# flight_comp_v3.net
KiCad netlist of a schematic drawn in EAGLE
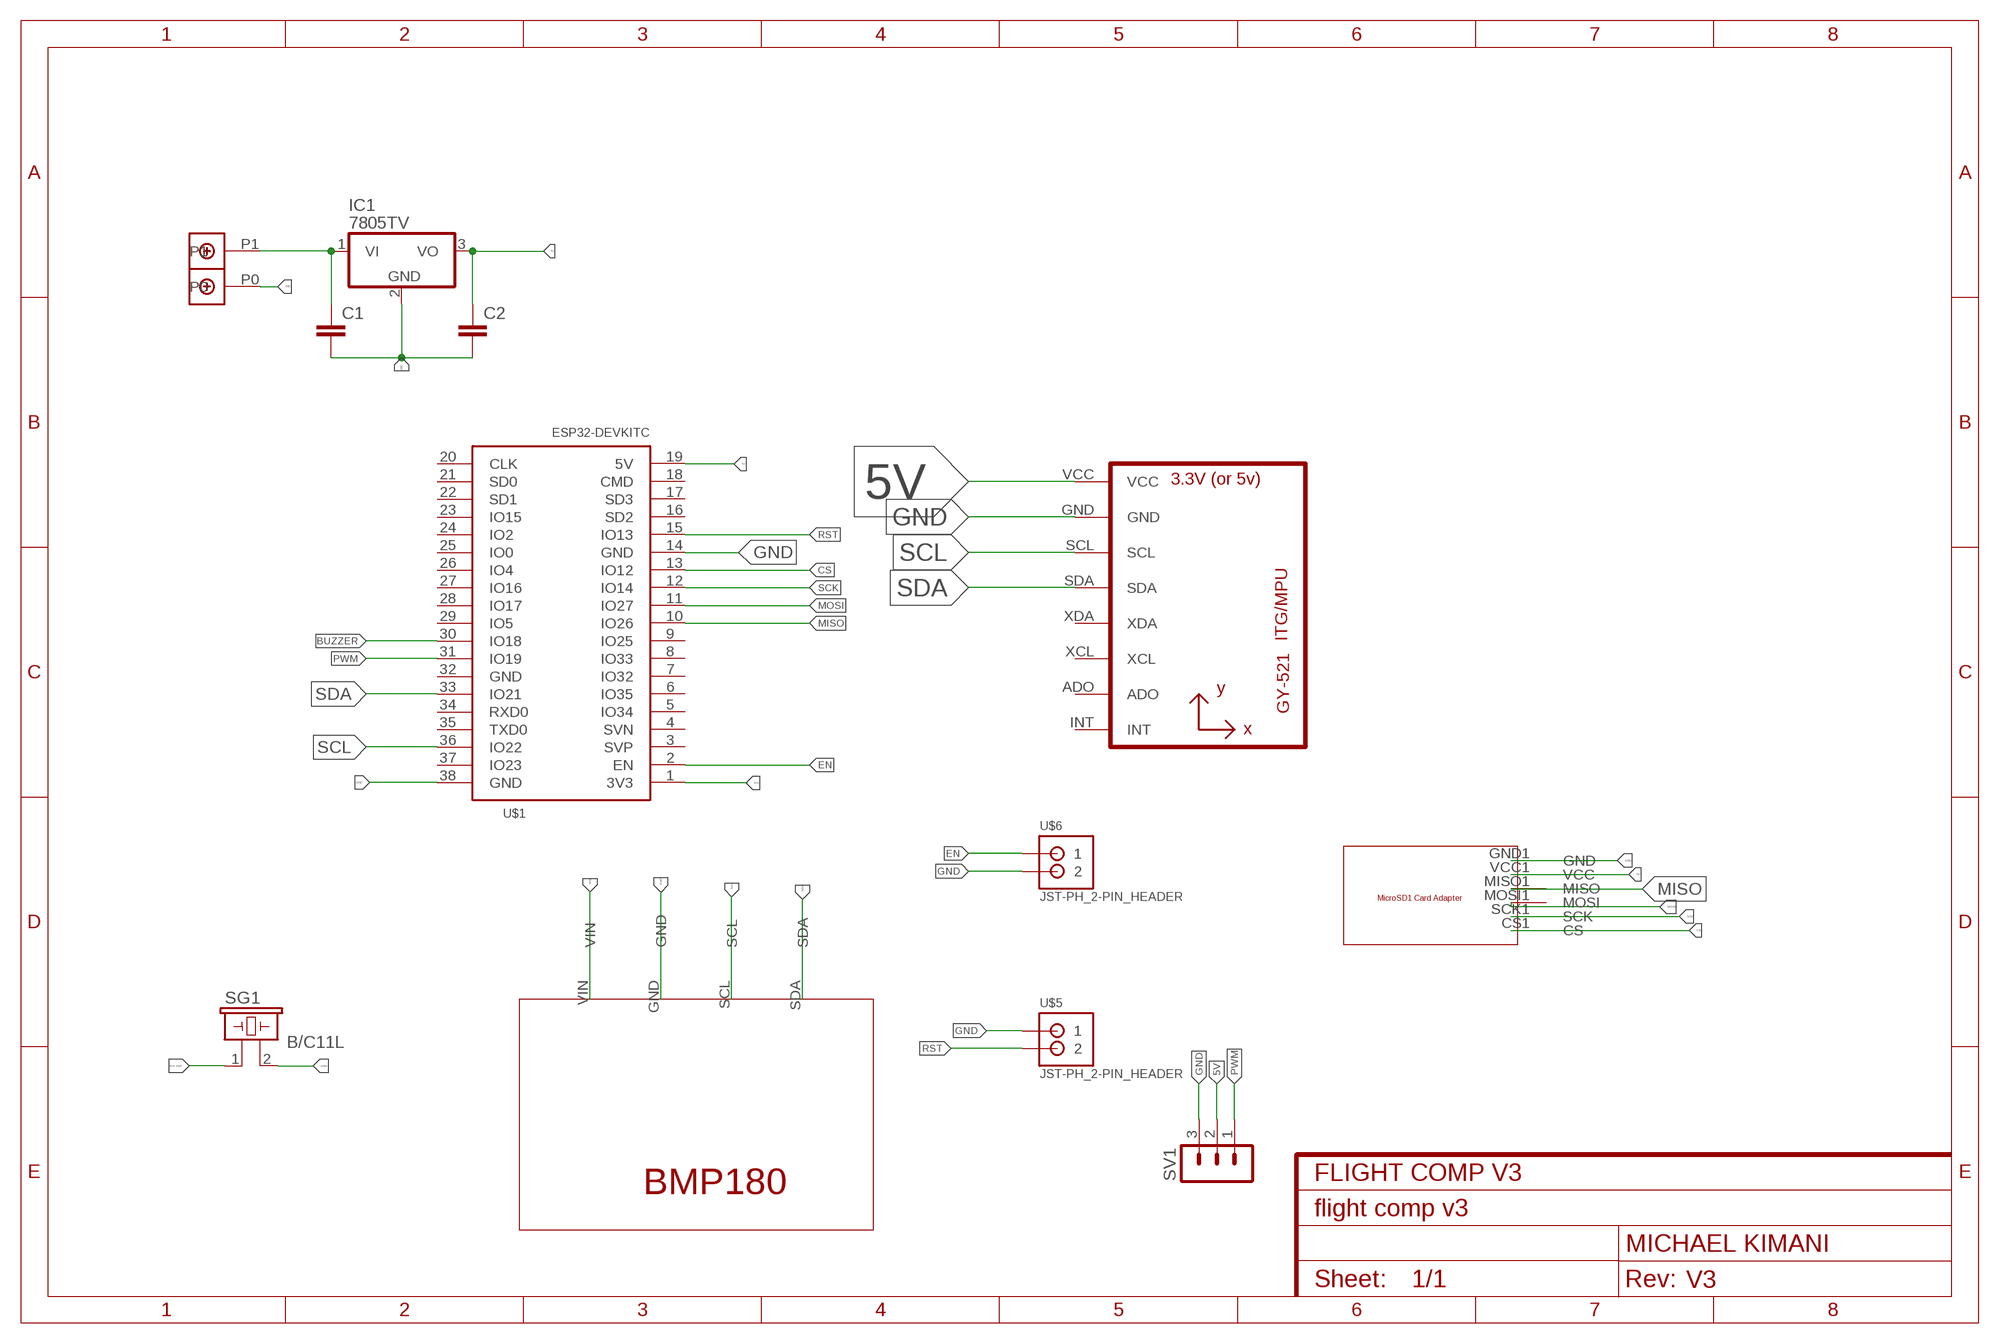
[diagram p0: schematic, sheet 1]

(export (version "E")
  (design (tool "Eeschema 10.0.6"))
  (components
    (comp (ref "C1")
      (value "C2,5-3")
      (footprint "eagle-import:C2.5-3")
      (libsource (lib "eagle-import") (part "C2,5-3"))
    )
    (comp (ref "C2")
      (value "C2,5-3")
      (footprint "eagle-import:C2.5-3")
      (libsource (lib "eagle-import") (part "C2,5-3"))
    )
    (comp (ref "IC1")
      (value "7805TV")
      (footprint "eagle-import:TO220V")
      (libsource (lib "eagle-import") (part "78TV05"))
    )
    (comp (ref "SG1")
      (value "B/C11L")
      (footprint "eagle-import:B_C11L")
      (libsource (lib "eagle-import") (part "B/C11L"))
    )
    (comp (ref "SV1")
      (value "MA03-1")
      (footprint "eagle-import:MA03-1")
      (libsource (lib "eagle-import") (part "MA03-1"))
    )
    (comp (ref "U$1")
      (value "ESP32DEVKITC")
      (footprint "eagle-import:ESP32-DEVKITC")
      (libsource (lib "eagle-import") (part "ESP32DEVKITC"))
    )
    (comp (ref "U$2")
      (value "MICROSDADAPTER")
      (footprint "eagle-import:MICROSDADAPTER")
      (libsource (lib "eagle-import") (part "MICROSDADAPTER"))
    )
    (comp (ref "U$3")
      (value "BMP180")
      (footprint "eagle-import:BMP180")
      (libsource (lib "eagle-import") (part "BMP180"))
    )
    (comp (ref "U$4")
      (value "DBCONN-1X2")
      (footprint "eagle-import:DBCONN-1X2")
      (libsource (lib "eagle-import") (part "DBCONN-1X2"))
    )
    (comp (ref "U$5")
      (value "JST-PH_2-PIN_HEADER")
      (footprint "eagle-import:JST_B2B-PH_HEADER")
      (libsource (lib "eagle-import") (part "JST-PH_2-PIN_HEADER"))
    )
    (comp (ref "U$6")
      (value "JST-PH_2-PIN_HEADER")
      (footprint "eagle-import:JST_B2B-PH_HEADER")
      (libsource (lib "eagle-import") (part "JST-PH_2-PIN_HEADER"))
    )
    (comp (ref "U1")
      (value "GY-521MPU6050")
      (footprint "eagle-import:GY-521")
      (libsource (lib "eagle-import") (part "GY-521MPU6050"))
    )
  )
  (nets
    (net (code "1") (name "3V3") (class "Default")
      (node (ref "U$1") (pin "1") (pinfunction "3V3_1") (pintype "bidirectional"))
      (node (ref "U$3") (pin "VIN") (pinfunction "VIN_VIN") (pintype "bidirectional"))
    )
    (net (code "2") (name "5V") (class "Default")
      (node (ref "C2") (pin "1") (pinfunction "1_1") (pintype "passive"))
      (node (ref "IC1") (pin "3") (pinfunction "VO_3") (pintype "passive"))
      (node (ref "SV1") (pin "2") (pinfunction "2_2") (pintype "passive"))
      (node (ref "U$1") (pin "19") (pinfunction "5V_19") (pintype "bidirectional"))
      (node (ref "U$2") (pin "VCC1") (pinfunction "VCC_VCC1") (pintype "bidirectional"))
      (node (ref "U1") (pin "VCC") (pinfunction "VCC_VCC") (pintype "bidirectional"))
    )
    (net (code "3") (name "BUZZER") (class "Default")
      (node (ref "SG1") (pin "1") (pinfunction "1_1") (pintype "passive"))
      (node (ref "U$1") (pin "30") (pinfunction "IO18_30") (pintype "bidirectional"))
    )
    (net (code "4") (name "CS") (class "Default")
      (node (ref "U$1") (pin "13") (pinfunction "IO12_13") (pintype "bidirectional"))
      (node (ref "U$2") (pin "CS1") (pinfunction "CS_CS1") (pintype "bidirectional"))
    )
    (net (code "5") (name "EN") (class "Default")
      (node (ref "U$1") (pin "2") (pinfunction "EN_2") (pintype "bidirectional"))
      (node (ref "U$6") (pin "P1") (pinfunction "1_P1") (pintype "bidirectional"))
    )
    (net (code "6") (name "GND") (class "Default")
      (node (ref "C1") (pin "2") (pinfunction "2_2") (pintype "passive"))
      (node (ref "C2") (pin "2") (pinfunction "2_2") (pintype "passive"))
      (node (ref "IC1") (pin "2") (pinfunction "GND_2") (pintype "passive"))
      (node (ref "SG1") (pin "2") (pinfunction "2_2") (pintype "passive"))
      (node (ref "SV1") (pin "3") (pinfunction "3_3") (pintype "passive"))
      (node (ref "U$1") (pin "14") (pinfunction "GND_14") (pintype "bidirectional"))
      (node (ref "U$1") (pin "38") (pinfunction "GND_38") (pintype "bidirectional"))
      (node (ref "U$2") (pin "GND1") (pinfunction "GND_GND1") (pintype "bidirectional"))
      (node (ref "U$3") (pin "GND") (pinfunction "GND_GND") (pintype "bidirectional"))
      (node (ref "U$4") (pin "P0") (pinfunction "P0_P0") (pintype "bidirectional"))
      (node (ref "U$5") (pin "P1") (pinfunction "1_P1") (pintype "bidirectional"))
      (node (ref "U$6") (pin "P2") (pinfunction "2_P2") (pintype "bidirectional"))
      (node (ref "U1") (pin "GND") (pinfunction "GND_GND") (pintype "bidirectional"))
    )
    (net (code "7") (name "MISO") (class "Default")
      (node (ref "U$1") (pin "10") (pinfunction "IO26_10") (pintype "bidirectional"))
      (node (ref "U$2") (pin "MISO1") (pinfunction "MISO_MISO1") (pintype "bidirectional"))
    )
    (net (code "8") (name "MOSI") (class "Default")
      (node (ref "U$1") (pin "11") (pinfunction "IO27_11") (pintype "bidirectional"))
      (node (ref "U$2") (pin "MOSI1") (pinfunction "MOSI_MOSI1") (pintype "bidirectional"))
    )
    (net (code "9") (name "Net-(IC1-VI)") (class "Default")
      (node (ref "C1") (pin "1") (pinfunction "1_1") (pintype "passive"))
      (node (ref "IC1") (pin "1") (pinfunction "VI_1") (pintype "input"))
      (node (ref "U$4") (pin "P1") (pinfunction "P1_P1") (pintype "bidirectional"))
    )
    (net (code "10") (name "PWM") (class "Default")
      (node (ref "SV1") (pin "1") (pinfunction "1_1") (pintype "passive"))
      (node (ref "U$1") (pin "31") (pinfunction "IO19_31") (pintype "bidirectional"))
    )
    (net (code "11") (name "RST") (class "Default")
      (node (ref "U$1") (pin "15") (pinfunction "IO13_15") (pintype "bidirectional"))
      (node (ref "U$5") (pin "P2") (pinfunction "2_P2") (pintype "bidirectional"))
    )
    (net (code "12") (name "SCK") (class "Default")
      (node (ref "U$1") (pin "12") (pinfunction "IO14_12") (pintype "bidirectional"))
      (node (ref "U$2") (pin "SCK1") (pinfunction "SCK_SCK1") (pintype "bidirectional"))
    )
    (net (code "13") (name "SCL") (class "Default")
      (node (ref "U$1") (pin "36") (pinfunction "IO22_36") (pintype "bidirectional"))
      (node (ref "U$3") (pin "SCL") (pinfunction "SCL_SCL") (pintype "bidirectional"))
      (node (ref "U1") (pin "SCL") (pinfunction "SCL_SCL") (pintype "bidirectional"))
    )
    (net (code "14") (name "SDA") (class "Default")
      (node (ref "U$1") (pin "33") (pinfunction "IO21_33") (pintype "bidirectional"))
      (node (ref "U$3") (pin "SDA") (pinfunction "SDA_SDA") (pintype "bidirectional"))
      (node (ref "U1") (pin "SDA") (pinfunction "SDA_SDA") (pintype "bidirectional"))
    )
    (net (code "15") (name "unconnected-(U$1-CLK-Pad20)") (class "Default")
      (node (ref "U$1") (pin "20") (pinfunction "CLK_20") (pintype "bidirectional"))
    )
    (net (code "16") (name "unconnected-(U$1-CMD-Pad18)") (class "Default")
      (node (ref "U$1") (pin "18") (pinfunction "CMD_18") (pintype "bidirectional"))
    )
    (net (code "17") (name "unconnected-(U$1-GND-Pad32)") (class "Default")
      (node (ref "U$1") (pin "32") (pinfunction "GND_32") (pintype "bidirectional"))
    )
    (net (code "18") (name "unconnected-(U$1-IO0-Pad25)") (class "Default")
      (node (ref "U$1") (pin "25") (pinfunction "IO0_25") (pintype "bidirectional"))
    )
    (net (code "19") (name "unconnected-(U$1-IO2-Pad24)") (class "Default")
      (node (ref "U$1") (pin "24") (pinfunction "IO2_24") (pintype "bidirectional"))
    )
    (net (code "20") (name "unconnected-(U$1-IO4-Pad26)") (class "Default")
      (node (ref "U$1") (pin "26") (pinfunction "IO4_26") (pintype "bidirectional"))
    )
    (net (code "21") (name "unconnected-(U$1-IO5-Pad29)") (class "Default")
      (node (ref "U$1") (pin "29") (pinfunction "IO5_29") (pintype "bidirectional"))
    )
    (net (code "22") (name "unconnected-(U$1-IO15-Pad23)") (class "Default")
      (node (ref "U$1") (pin "23") (pinfunction "IO15_23") (pintype "bidirectional"))
    )
    (net (code "23") (name "unconnected-(U$1-IO16-Pad27)") (class "Default")
      (node (ref "U$1") (pin "27") (pinfunction "IO16_27") (pintype "bidirectional"))
    )
    (net (code "24") (name "unconnected-(U$1-IO17-Pad28)") (class "Default")
      (node (ref "U$1") (pin "28") (pinfunction "IO17_28") (pintype "bidirectional"))
    )
    (net (code "25") (name "unconnected-(U$1-IO23-Pad37)") (class "Default")
      (node (ref "U$1") (pin "37") (pinfunction "IO23_37") (pintype "bidirectional"))
    )
    (net (code "26") (name "unconnected-(U$1-IO25-Pad9)") (class "Default")
      (node (ref "U$1") (pin "9") (pinfunction "IO25_9") (pintype "bidirectional"))
    )
    (net (code "27") (name "unconnected-(U$1-IO32-Pad7)") (class "Default")
      (node (ref "U$1") (pin "7") (pinfunction "IO32_7") (pintype "bidirectional"))
    )
    (net (code "28") (name "unconnected-(U$1-IO33-Pad8)") (class "Default")
      (node (ref "U$1") (pin "8") (pinfunction "IO33_8") (pintype "bidirectional"))
    )
    (net (code "29") (name "unconnected-(U$1-IO34-Pad5)") (class "Default")
      (node (ref "U$1") (pin "5") (pinfunction "IO34_5") (pintype "bidirectional"))
    )
    (net (code "30") (name "unconnected-(U$1-IO35-Pad6)") (class "Default")
      (node (ref "U$1") (pin "6") (pinfunction "IO35_6") (pintype "bidirectional"))
    )
    (net (code "31") (name "unconnected-(U$1-RXD0-Pad34)") (class "Default")
      (node (ref "U$1") (pin "34") (pinfunction "RXD0_34") (pintype "bidirectional"))
    )
    (net (code "32") (name "unconnected-(U$1-SD0-Pad21)") (class "Default")
      (node (ref "U$1") (pin "21") (pinfunction "SD0_21") (pintype "bidirectional"))
    )
    (net (code "33") (name "unconnected-(U$1-SD1-Pad22)") (class "Default")
      (node (ref "U$1") (pin "22") (pinfunction "SD1_22") (pintype "bidirectional"))
    )
    (net (code "34") (name "unconnected-(U$1-SD2-Pad16)") (class "Default")
      (node (ref "U$1") (pin "16") (pinfunction "SD2_16") (pintype "bidirectional"))
    )
    (net (code "35") (name "unconnected-(U$1-SD3-Pad17)") (class "Default")
      (node (ref "U$1") (pin "17") (pinfunction "SD3_17") (pintype "bidirectional"))
    )
    (net (code "36") (name "unconnected-(U$1-SVN-Pad4)") (class "Default")
      (node (ref "U$1") (pin "4") (pinfunction "SVN_4") (pintype "bidirectional"))
    )
    (net (code "37") (name "unconnected-(U$1-SVP-Pad3)") (class "Default")
      (node (ref "U$1") (pin "3") (pinfunction "SVP_3") (pintype "bidirectional"))
    )
    (net (code "38") (name "unconnected-(U$1-TXD0-Pad35)") (class "Default")
      (node (ref "U$1") (pin "35") (pinfunction "TXD0_35") (pintype "bidirectional"))
    )
    (net (code "39") (name "unconnected-(U1-PadADO)") (class "Default")
      (node (ref "U1") (pin "ADO") (pinfunction "ADO_ADO") (pintype "bidirectional"))
    )
    (net (code "40") (name "unconnected-(U1-PadINT)") (class "Default")
      (node (ref "U1") (pin "INT") (pinfunction "INT_INT") (pintype "bidirectional"))
    )
    (net (code "41") (name "unconnected-(U1-PadXCL)") (class "Default")
      (node (ref "U1") (pin "XCL") (pinfunction "XCL_XCL") (pintype "bidirectional"))
    )
    (net (code "42") (name "unconnected-(U1-PadXDA)") (class "Default")
      (node (ref "U1") (pin "XDA") (pinfunction "XDA_XDA") (pintype "bidirectional"))
    )
  )
)
